# OZ440-SE100-CAR003_Sheet2.net
KiCad netlist of a schematic drawn in Altium Designer
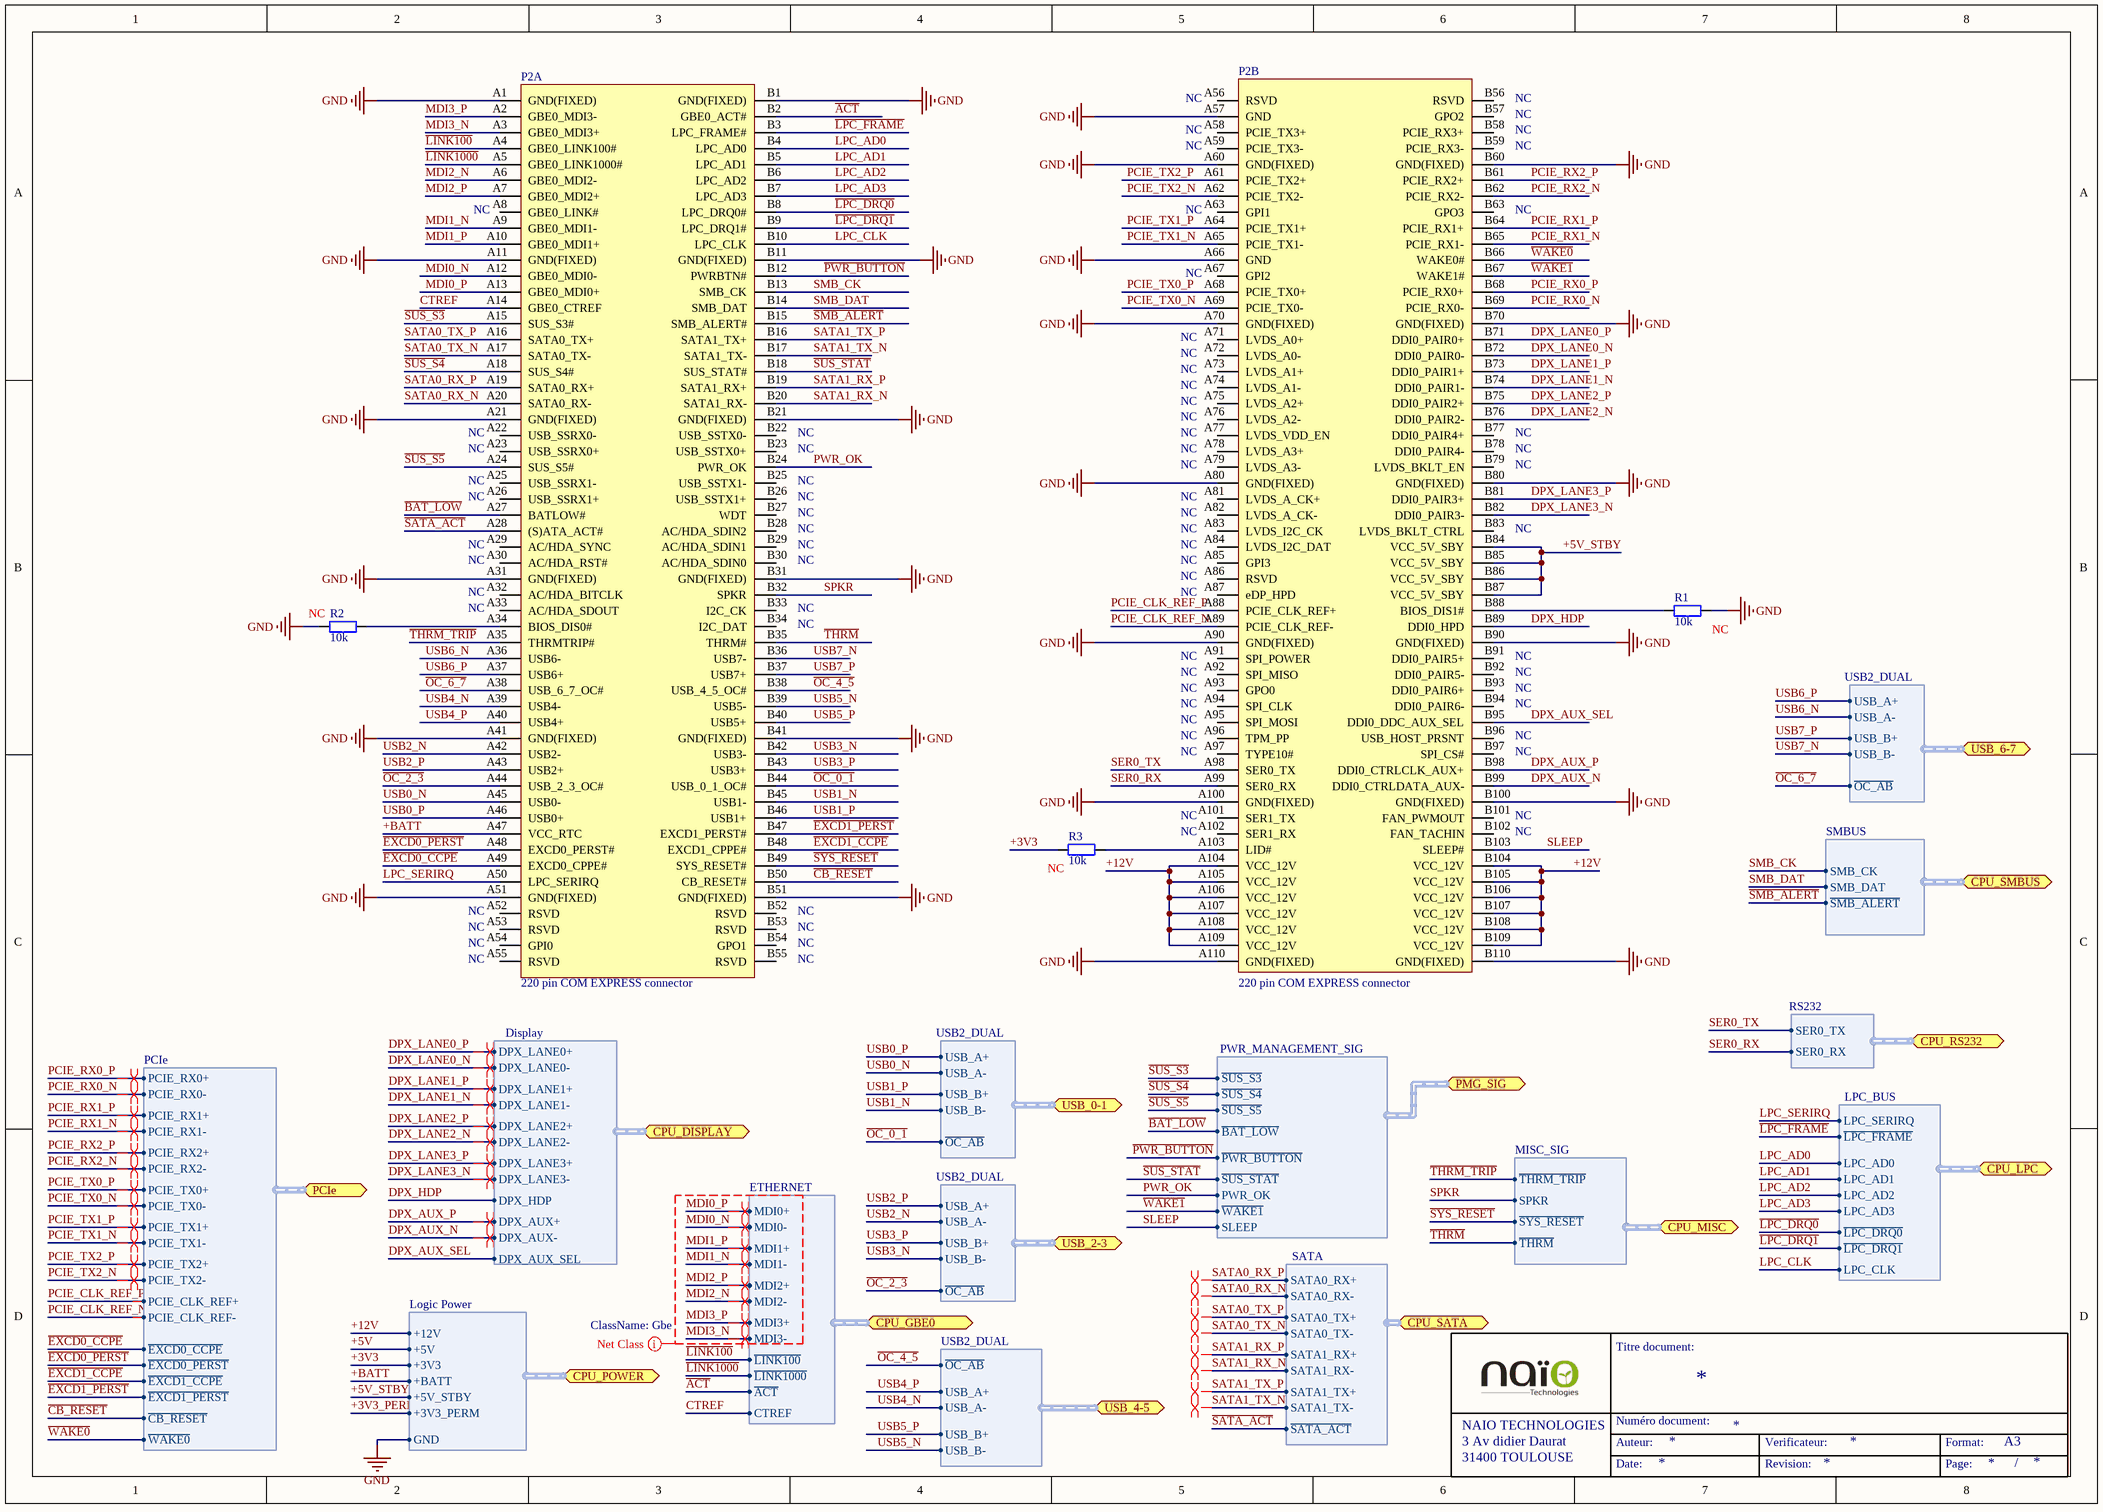
[diagram p0: OZ440-SE100-CAR003_Sheet2.SchDoc]

(export (version "E")
  (design (tool "Eeschema 10.0.6"))
  (components
    (comp (ref "P2")
      (value "CONN-SPE-220P_AMP_3-1827253-6")
      (footprint "CONN-SPE_AMP_3-1827253-6")
      (description "type 10 com express connector")
      (fields
        (field (name "DISPLAYED REFERENCE") "220 pin COM EXPRESS connector")
        (field (name "MANUFACTURER") "TE connectivity")
      )
      (libsource (lib "lib_NAIO") (part "CONN-SPE-220P_AMP_3-1827253-6"))
    )
    (comp (ref "R1")
      (value "RES-SMD")
      (footprint "R0805-STD")
      (description "10k Ohm 0805 SMD resistor")
      (fields
        (field (name "DISPLAYED REFERENCE") "10k")
        (field (name "TOLERANCE") "1 %")
        (field (name "MANUFACTURER") "Vishay")
      )
      (libsource (lib "lib_NAIO") (part "RES-SMD"))
    )
    (comp (ref "R2")
      (value "RES-SMD")
      (footprint "R0805-STD")
      (description "10k Ohm 0805 SMD resistor")
      (fields
        (field (name "DISPLAYED REFERENCE") "10k")
        (field (name "TOLERANCE") "1 %")
        (field (name "MANUFACTURER") "Vishay")
      )
      (libsource (lib "") (part "RES-SMD_1"))
    )
    (comp (ref "R3")
      (value "RES-SMD")
      (footprint "R0805-STD")
      (description "10k Ohm 0805 SMD resistor")
      (fields
        (field (name "DISPLAYED REFERENCE") "10k")
        (field (name "TOLERANCE") "1 %")
        (field (name "MANUFACTURER") "Vishay")
      )
      (libsource (lib "lib_NAIO") (part "RES-SMD"))
    )
  )
  (nets
    (net (code "13") (name "/+3V3") (class "Default")
      (node (ref "R3") (pin "2") (pinfunction "2_2") (pintype "passive"))
    )
    (net (code "16") (name "/+5V_STBY") (class "Default")
      (node (ref "P2") (pin "B84") (pinfunction "VCC_5V_SBY_B84") (pintype "passive"))
      (node (ref "P2") (pin "B85") (pinfunction "VCC_5V_SBY_B85") (pintype "passive"))
      (node (ref "P2") (pin "B86") (pinfunction "VCC_5V_SBY_B86") (pintype "passive"))
      (node (ref "P2") (pin "B87") (pinfunction "VCC_5V_SBY_B87") (pintype "passive"))
    )
    (net (code "17") (name "/+12V") (class "Default")
      (node (ref "P2") (pin "A104") (pinfunction "VCC_12V_A104") (pintype "passive"))
      (node (ref "P2") (pin "A105") (pinfunction "VCC_12V_A105") (pintype "passive"))
      (node (ref "P2") (pin "A106") (pinfunction "VCC_12V_A106") (pintype "passive"))
      (node (ref "P2") (pin "A107") (pinfunction "VCC_12V_A107") (pintype "passive"))
      (node (ref "P2") (pin "A108") (pinfunction "VCC_12V_A108") (pintype "passive"))
      (node (ref "P2") (pin "A109") (pinfunction "VCC_12V_A109") (pintype "passive"))
      (node (ref "P2") (pin "B104") (pinfunction "VCC_12V_B104") (pintype "passive"))
      (node (ref "P2") (pin "B105") (pinfunction "VCC_12V_B105") (pintype "passive"))
      (node (ref "P2") (pin "B106") (pinfunction "VCC_12V_B106") (pintype "passive"))
      (node (ref "P2") (pin "B107") (pinfunction "VCC_12V_B107") (pintype "passive"))
      (node (ref "P2") (pin "B108") (pinfunction "VCC_12V_B108") (pintype "passive"))
      (node (ref "P2") (pin "B109") (pinfunction "VCC_12V_B109") (pintype "passive"))
    )
    (net (code "18") (name "/+BATT") (class "Default")
      (node (ref "P2") (pin "A47") (pinfunction "VCC_RTC_A47") (pintype "passive"))
    )
    (net (code "19") (name "/ACT") (class "Default")
      (node (ref "P2") (pin "B2") (pinfunction "GBE0_ACT#_B2") (pintype "passive"))
    )
    (net (code "20") (name "/BAT_LOW") (class "Default")
      (node (ref "P2") (pin "A27") (pinfunction "BATLOW#_A27") (pintype "passive"))
    )
    (net (code "21") (name "/CB_RESET") (class "Default")
      (node (ref "P2") (pin "B50") (pinfunction "CB_RESET#_B50") (pintype "passive"))
    )
    (net (code "22") (name "/CTREF") (class "Default")
      (node (ref "P2") (pin "A14") (pinfunction "GBE0_CTREF_A14") (pintype "passive"))
    )
    (net (code "23") (name "/DPX_AUX_N") (class "Default")
      (node (ref "P2") (pin "B99") (pinfunction "DDI0_CTRLDATA_AUX-_B99") (pintype "passive"))
    )
    (net (code "24") (name "/DPX_AUX_P") (class "Default")
      (node (ref "P2") (pin "B98") (pinfunction "DDI0_CTRLCLK_AUX+_B98") (pintype "passive"))
    )
    (net (code "25") (name "/DPX_AUX_SEL") (class "Default")
      (node (ref "P2") (pin "B95") (pinfunction "DDI0_DDC_AUX_SEL_B95") (pintype "passive"))
    )
    (net (code "26") (name "/DPX_HDP") (class "Default")
      (node (ref "P2") (pin "B89") (pinfunction "DDI0_HPD_B89") (pintype "passive"))
    )
    (net (code "27") (name "/DPX_LANE0_N") (class "Default")
      (node (ref "P2") (pin "B72") (pinfunction "DDI0_PAIR0-_B72") (pintype "passive"))
    )
    (net (code "28") (name "/DPX_LANE0_P") (class "Default")
      (node (ref "P2") (pin "B71") (pinfunction "DDI0_PAIR0+_B71") (pintype "passive"))
    )
    (net (code "29") (name "/DPX_LANE1_N") (class "Default")
      (node (ref "P2") (pin "B74") (pinfunction "DDI0_PAIR1-_B74") (pintype "passive"))
    )
    (net (code "30") (name "/DPX_LANE1_P") (class "Default")
      (node (ref "P2") (pin "B73") (pinfunction "DDI0_PAIR1+_B73") (pintype "passive"))
    )
    (net (code "31") (name "/DPX_LANE2_N") (class "Default")
      (node (ref "P2") (pin "B76") (pinfunction "DDI0_PAIR2-_B76") (pintype "passive"))
    )
    (net (code "32") (name "/DPX_LANE2_P") (class "Default")
      (node (ref "P2") (pin "B75") (pinfunction "DDI0_PAIR2+_B75") (pintype "passive"))
    )
    (net (code "33") (name "/DPX_LANE3_N") (class "Default")
      (node (ref "P2") (pin "B82") (pinfunction "DDI0_PAIR3-_B82") (pintype "passive"))
    )
    (net (code "34") (name "/DPX_LANE3_P") (class "Default")
      (node (ref "P2") (pin "B81") (pinfunction "DDI0_PAIR3+_B81") (pintype "passive"))
    )
    (net (code "35") (name "/EXCD0_CCPE") (class "Default")
      (node (ref "P2") (pin "A49") (pinfunction "EXCD0_CPPE#_A49") (pintype "passive"))
    )
    (net (code "36") (name "/EXCD0_PERST") (class "Default")
      (node (ref "P2") (pin "A48") (pinfunction "EXCD0_PERST#_A48") (pintype "passive"))
    )
    (net (code "37") (name "/EXCD1_CCPE") (class "Default")
      (node (ref "P2") (pin "B48") (pinfunction "EXCD1_CPPE#_B48") (pintype "passive"))
    )
    (net (code "38") (name "/EXCD1_PERST") (class "Default")
      (node (ref "P2") (pin "B47") (pinfunction "EXCD1_PERST#_B47") (pintype "passive"))
    )
    (net (code "39") (name "/LINK100") (class "Default")
      (node (ref "P2") (pin "A4") (pinfunction "GBE0_LINK100#_A4") (pintype "passive"))
    )
    (net (code "40") (name "/LINK1000") (class "Default")
      (node (ref "P2") (pin "A5") (pinfunction "GBE0_LINK1000#_A5") (pintype "passive"))
    )
    (net (code "41") (name "/LPC_AD0") (class "Default")
      (node (ref "P2") (pin "B4") (pinfunction "LPC_AD0_B4") (pintype "passive"))
    )
    (net (code "42") (name "/LPC_AD1") (class "Default")
      (node (ref "P2") (pin "B5") (pinfunction "LPC_AD1_B5") (pintype "passive"))
    )
    (net (code "43") (name "/LPC_AD2") (class "Default")
      (node (ref "P2") (pin "B6") (pinfunction "LPC_AD2_B6") (pintype "passive"))
    )
    (net (code "44") (name "/LPC_AD3") (class "Default")
      (node (ref "P2") (pin "B7") (pinfunction "LPC_AD3_B7") (pintype "passive"))
    )
    (net (code "45") (name "/LPC_CLK") (class "Default")
      (node (ref "P2") (pin "B10") (pinfunction "LPC_CLK_B10") (pintype "passive"))
    )
    (net (code "46") (name "/LPC_DRQ0") (class "Default")
      (node (ref "P2") (pin "B8") (pinfunction "LPC_DRQ0#_B8") (pintype "passive"))
    )
    (net (code "47") (name "/LPC_DRQ1") (class "Default")
      (node (ref "P2") (pin "B9") (pinfunction "LPC_DRQ1#_B9") (pintype "passive"))
    )
    (net (code "48") (name "/LPC_FRAME") (class "Default")
      (node (ref "P2") (pin "B3") (pinfunction "LPC_FRAME#_B3") (pintype "passive"))
    )
    (net (code "49") (name "/LPC_SERIRQ") (class "Default")
      (node (ref "P2") (pin "A50") (pinfunction "LPC_SERIRQ_A50") (pintype "passive"))
    )
    (net (code "50") (name "/MDI0_N") (class "Default")
      (node (ref "P2") (pin "A12") (pinfunction "GBE0_MDI0-_A12") (pintype "passive"))
    )
    (net (code "51") (name "/MDI0_P") (class "Default")
      (node (ref "P2") (pin "A13") (pinfunction "GBE0_MDI0+_A13") (pintype "passive"))
    )
    (net (code "52") (name "/MDI1_N") (class "Default")
      (node (ref "P2") (pin "A9") (pinfunction "GBE0_MDI1-_A9") (pintype "passive"))
    )
    (net (code "53") (name "/MDI1_P") (class "Default")
      (node (ref "P2") (pin "A10") (pinfunction "GBE0_MDI1+_A10") (pintype "passive"))
    )
    (net (code "54") (name "/MDI2_N") (class "Default")
      (node (ref "P2") (pin "A6") (pinfunction "GBE0_MDI2-_A6") (pintype "passive"))
    )
    (net (code "55") (name "/MDI2_P") (class "Default")
      (node (ref "P2") (pin "A7") (pinfunction "GBE0_MDI2+_A7") (pintype "passive"))
    )
    (net (code "56") (name "/MDI3_N") (class "Default")
      (node (ref "P2") (pin "A3") (pinfunction "GBE0_MDI3+_A3") (pintype "passive"))
    )
    (net (code "57") (name "/MDI3_P") (class "Default")
      (node (ref "P2") (pin "A2") (pinfunction "GBE0_MDI3-_A2") (pintype "passive"))
    )
    (net (code "58") (name "/OC_0_1") (class "Default")
      (node (ref "P2") (pin "B44") (pinfunction "USB_0_1_OC#_B44") (pintype "passive"))
    )
    (net (code "59") (name "/OC_2_3") (class "Default")
      (node (ref "P2") (pin "A44") (pinfunction "USB_2_3_OC#_A44") (pintype "passive"))
    )
    (net (code "60") (name "/OC_4_5") (class "Default")
      (node (ref "P2") (pin "B38") (pinfunction "USB_4_5_OC#_B38") (pintype "passive"))
    )
    (net (code "61") (name "/OC_6_7") (class "Default")
      (node (ref "P2") (pin "A38") (pinfunction "USB_6_7_OC#_A38") (pintype "passive"))
    )
    (net (code "62") (name "/PCIE_CLK_REF_N") (class "Default")
      (node (ref "P2") (pin "A89") (pinfunction "PCIE_CLK_REF-_A89") (pintype "passive"))
    )
    (net (code "63") (name "/PCIE_CLK_REF_P") (class "Default")
      (node (ref "P2") (pin "A88") (pinfunction "PCIE_CLK_REF+_A88") (pintype "passive"))
    )
    (net (code "64") (name "/PCIE_RX0_N") (class "Default")
      (node (ref "P2") (pin "B69") (pinfunction "PCIE_RX0-_B69") (pintype "passive"))
    )
    (net (code "65") (name "/PCIE_RX0_P") (class "Default")
      (node (ref "P2") (pin "B68") (pinfunction "PCIE_RX0+_B68") (pintype "passive"))
    )
    (net (code "66") (name "/PCIE_RX1_N") (class "Default")
      (node (ref "P2") (pin "B65") (pinfunction "PCIE_RX1-_B65") (pintype "passive"))
    )
    (net (code "67") (name "/PCIE_RX1_P") (class "Default")
      (node (ref "P2") (pin "B64") (pinfunction "PCIE_RX1+_B64") (pintype "passive"))
    )
    (net (code "68") (name "/PCIE_RX2_N") (class "Default")
      (node (ref "P2") (pin "B62") (pinfunction "PCIE_RX2-_B62") (pintype "passive"))
    )
    (net (code "69") (name "/PCIE_RX2_P") (class "Default")
      (node (ref "P2") (pin "B61") (pinfunction "PCIE_RX2+_B61") (pintype "passive"))
    )
    (net (code "70") (name "/PCIE_TX0_N") (class "Default")
      (node (ref "P2") (pin "A69") (pinfunction "PCIE_TX0-_A69") (pintype "passive"))
    )
    (net (code "71") (name "/PCIE_TX0_P") (class "Default")
      (node (ref "P2") (pin "A68") (pinfunction "PCIE_TX0+_A68") (pintype "passive"))
    )
    (net (code "72") (name "/PCIE_TX1_N") (class "Default")
      (node (ref "P2") (pin "A65") (pinfunction "PCIE_TX1-_A65") (pintype "passive"))
    )
    (net (code "73") (name "/PCIE_TX1_P") (class "Default")
      (node (ref "P2") (pin "A64") (pinfunction "PCIE_TX1+_A64") (pintype "passive"))
    )
    (net (code "74") (name "/PCIE_TX2_N") (class "Default")
      (node (ref "P2") (pin "A62") (pinfunction "PCIE_TX2-_A62") (pintype "passive"))
    )
    (net (code "75") (name "/PCIE_TX2_P") (class "Default")
      (node (ref "P2") (pin "A61") (pinfunction "PCIE_TX2+_A61") (pintype "passive"))
    )
    (net (code "76") (name "/PWR_BUTTON") (class "Default")
      (node (ref "P2") (pin "B12") (pinfunction "PWRBTN#_B12") (pintype "passive"))
    )
    (net (code "77") (name "/PWR_OK") (class "Default")
      (node (ref "P2") (pin "B24") (pinfunction "PWR_OK_B24") (pintype "passive"))
    )
    (net (code "78") (name "/SATA0_RX_N") (class "Default")
      (node (ref "P2") (pin "A20") (pinfunction "SATA0_RX-_A20") (pintype "passive"))
    )
    (net (code "79") (name "/SATA0_RX_P") (class "Default")
      (node (ref "P2") (pin "A19") (pinfunction "SATA0_RX+_A19") (pintype "passive"))
    )
    (net (code "80") (name "/SATA0_TX_N") (class "Default")
      (node (ref "P2") (pin "A17") (pinfunction "SATA0_TX-_A17") (pintype "passive"))
    )
    (net (code "81") (name "/SATA0_TX_P") (class "Default")
      (node (ref "P2") (pin "A16") (pinfunction "SATA0_TX+_A16") (pintype "passive"))
    )
    (net (code "82") (name "/SATA1_RX_N") (class "Default")
      (node (ref "P2") (pin "B20") (pinfunction "SATA1_RX-_B20") (pintype "passive"))
    )
    (net (code "83") (name "/SATA1_RX_P") (class "Default")
      (node (ref "P2") (pin "B19") (pinfunction "SATA1_RX+_B19") (pintype "passive"))
    )
    (net (code "84") (name "/SATA1_TX_N") (class "Default")
      (node (ref "P2") (pin "B17") (pinfunction "SATA1_TX-_B17") (pintype "passive"))
    )
    (net (code "85") (name "/SATA1_TX_P") (class "Default")
      (node (ref "P2") (pin "B16") (pinfunction "SATA1_TX+_B16") (pintype "passive"))
    )
    (net (code "86") (name "/SATA_ACT") (class "Default")
      (node (ref "P2") (pin "A28") (pinfunction "(S)ATA_ACT#_A28") (pintype "passive"))
    )
    (net (code "87") (name "/SER0_RX") (class "Default")
      (node (ref "P2") (pin "A99") (pinfunction "SER0_RX_A99") (pintype "passive"))
    )
    (net (code "88") (name "/SER0_TX") (class "Default")
      (node (ref "P2") (pin "A98") (pinfunction "SER0_TX_A98") (pintype "passive"))
    )
    (net (code "89") (name "/SLEEP") (class "Default")
      (node (ref "P2") (pin "B103") (pinfunction "SLEEP#_B103") (pintype "passive"))
    )
    (net (code "90") (name "/SMB_ALERT") (class "Default")
      (node (ref "P2") (pin "B15") (pinfunction "SMB_ALERT#_B15") (pintype "passive"))
    )
    (net (code "91") (name "/SMB_CK") (class "Default")
      (node (ref "P2") (pin "B13") (pinfunction "SMB_CK_B13") (pintype "passive"))
    )
    (net (code "92") (name "/SMB_DAT") (class "Default")
      (node (ref "P2") (pin "B14") (pinfunction "SMB_DAT_B14") (pintype "passive"))
    )
    (net (code "93") (name "/SPKR") (class "Default")
      (node (ref "P2") (pin "B32") (pinfunction "SPKR_B32") (pintype "passive"))
    )
    (net (code "94") (name "/SUS_S3") (class "Default")
      (node (ref "P2") (pin "A15") (pinfunction "SUS_S3#_A15") (pintype "passive"))
    )
    (net (code "95") (name "/SUS_S4") (class "Default")
      (node (ref "P2") (pin "A18") (pinfunction "SUS_S4#_A18") (pintype "passive"))
    )
    (net (code "96") (name "/SUS_S5") (class "Default")
      (node (ref "P2") (pin "A24") (pinfunction "SUS_S5#_A24") (pintype "passive"))
    )
    (net (code "97") (name "/SUS_STAT") (class "Default")
      (node (ref "P2") (pin "B18") (pinfunction "SUS_STAT#_B18") (pintype "passive"))
    )
    (net (code "98") (name "/SYS_RESET") (class "Default")
      (node (ref "P2") (pin "B49") (pinfunction "SYS_RESET#_B49") (pintype "passive"))
    )
    (net (code "99") (name "/THRM") (class "Default")
      (node (ref "P2") (pin "B35") (pinfunction "THRM#_B35") (pintype "passive"))
    )
    (net (code "100") (name "/THRM_TRIP") (class "Default")
      (node (ref "P2") (pin "A35") (pinfunction "THRMTRIP#_A35") (pintype "passive"))
    )
    (net (code "101") (name "/USB0_N") (class "Default")
      (node (ref "P2") (pin "A45") (pinfunction "USB0-_A45") (pintype "passive"))
    )
    (net (code "102") (name "/USB0_P") (class "Default")
      (node (ref "P2") (pin "A46") (pinfunction "USB0+_A46") (pintype "passive"))
    )
    (net (code "103") (name "/USB1_N") (class "Default")
      (node (ref "P2") (pin "B45") (pinfunction "USB1-_B45") (pintype "passive"))
    )
    (net (code "104") (name "/USB1_P") (class "Default")
      (node (ref "P2") (pin "B46") (pinfunction "USB1+_B46") (pintype "passive"))
    )
    (net (code "105") (name "/USB2_N") (class "Default")
      (node (ref "P2") (pin "A42") (pinfunction "USB2-_A42") (pintype "passive"))
    )
    (net (code "106") (name "/USB2_P") (class "Default")
      (node (ref "P2") (pin "A43") (pinfunction "USB2+_A43") (pintype "passive"))
    )
    (net (code "107") (name "/USB3_N") (class "Default")
      (node (ref "P2") (pin "B42") (pinfunction "USB3-_B42") (pintype "passive"))
    )
    (net (code "108") (name "/USB3_P") (class "Default")
      (node (ref "P2") (pin "B43") (pinfunction "USB3+_B43") (pintype "passive"))
    )
    (net (code "109") (name "/USB4_N") (class "Default")
      (node (ref "P2") (pin "A39") (pinfunction "USB4-_A39") (pintype "passive"))
    )
    (net (code "110") (name "/USB4_P") (class "Default")
      (node (ref "P2") (pin "A40") (pinfunction "USB4+_A40") (pintype "passive"))
    )
    (net (code "111") (name "/USB5_N") (class "Default")
      (node (ref "P2") (pin "B39") (pinfunction "USB5-_B39") (pintype "passive"))
    )
    (net (code "112") (name "/USB5_P") (class "Default")
      (node (ref "P2") (pin "B40") (pinfunction "USB5+_B40") (pintype "passive"))
    )
    (net (code "113") (name "/USB6_N") (class "Default")
      (node (ref "P2") (pin "A36") (pinfunction "USB6-_A36") (pintype "passive"))
    )
    (net (code "114") (name "/USB6_P") (class "Default")
      (node (ref "P2") (pin "A37") (pinfunction "USB6+_A37") (pintype "passive"))
    )
    (net (code "115") (name "/USB7_N") (class "Default")
      (node (ref "P2") (pin "B36") (pinfunction "USB7-_B36") (pintype "passive"))
    )
    (net (code "116") (name "/USB7_P") (class "Default")
      (node (ref "P2") (pin "B37") (pinfunction "USB7+_B37") (pintype "passive"))
    )
    (net (code "117") (name "/WAKE0") (class "Default")
      (node (ref "P2") (pin "B66") (pinfunction "WAKE0#_B66") (pintype "passive"))
    )
    (net (code "118") (name "/WAKE1") (class "Default")
      (node (ref "P2") (pin "B67") (pinfunction "WAKE1#_B67") (pintype "passive"))
    )
    (net (code "130") (name "GND") (class "Default")
      (node (ref "P2") (pin "A1") (pinfunction "GND(FIXED)_A1") (pintype "passive"))
      (node (ref "P2") (pin "A100") (pinfunction "GND(FIXED)_A100") (pintype "passive"))
      (node (ref "P2") (pin "A11") (pinfunction "GND(FIXED)_A11") (pintype "passive"))
      (node (ref "P2") (pin "A110") (pinfunction "GND(FIXED)_A110") (pintype "passive"))
      (node (ref "P2") (pin "A21") (pinfunction "GND(FIXED)_A21") (pintype "passive"))
      (node (ref "P2") (pin "A31") (pinfunction "GND(FIXED)_A31") (pintype "passive"))
      (node (ref "P2") (pin "A41") (pinfunction "GND(FIXED)_A41") (pintype "passive"))
      (node (ref "P2") (pin "A51") (pinfunction "GND(FIXED)_A51") (pintype "passive"))
      (node (ref "P2") (pin "A57") (pinfunction "GND_A57") (pintype "passive"))
      (node (ref "P2") (pin "A60") (pinfunction "GND(FIXED)_A60") (pintype "passive"))
      (node (ref "P2") (pin "A66") (pinfunction "GND_A66") (pintype "passive"))
      (node (ref "P2") (pin "A70") (pinfunction "GND(FIXED)_A70") (pintype "passive"))
      (node (ref "P2") (pin "A80") (pinfunction "GND(FIXED)_A80") (pintype "passive"))
      (node (ref "P2") (pin "A90") (pinfunction "GND(FIXED)_A90") (pintype "passive"))
      (node (ref "P2") (pin "B1") (pinfunction "GND(FIXED)_B1") (pintype "passive"))
      (node (ref "P2") (pin "B100") (pinfunction "GND(FIXED)_B100") (pintype "passive"))
      (node (ref "P2") (pin "B11") (pinfunction "GND(FIXED)_B11") (pintype "passive"))
      (node (ref "P2") (pin "B110") (pinfunction "GND(FIXED)_B110") (pintype "passive"))
      (node (ref "P2") (pin "B21") (pinfunction "GND(FIXED)_B21") (pintype "passive"))
      (node (ref "P2") (pin "B31") (pinfunction "GND(FIXED)_B31") (pintype "passive"))
      (node (ref "P2") (pin "B41") (pinfunction "GND(FIXED)_B41") (pintype "passive"))
      (node (ref "P2") (pin "B51") (pinfunction "GND(FIXED)_B51") (pintype "passive"))
      (node (ref "P2") (pin "B60") (pinfunction "GND(FIXED)_B60") (pintype "passive"))
      (node (ref "P2") (pin "B70") (pinfunction "GND(FIXED)_B70") (pintype "passive"))
      (node (ref "P2") (pin "B80") (pinfunction "GND(FIXED)_B80") (pintype "passive"))
      (node (ref "P2") (pin "B90") (pinfunction "GND(FIXED)_B90") (pintype "passive"))
      (node (ref "R1") (pin "1") (pinfunction "1_1") (pintype "passive"))
      (node (ref "R2") (pin "1") (pinfunction "1_1") (pintype "passive"))
    )
    (net (code "131") (name "Net-(P2A-BIOS_DIS0#)") (class "Default")
      (node (ref "P2") (pin "A34") (pinfunction "BIOS_DIS0#_A34") (pintype "passive"))
      (node (ref "R2") (pin "2") (pinfunction "2_2") (pintype "passive"))
    )
    (net (code "132") (name "Net-(P2B-BIOS_DIS1#)") (class "Default")
      (node (ref "P2") (pin "B88") (pinfunction "BIOS_DIS1#_B88") (pintype "passive"))
      (node (ref "R1") (pin "2") (pinfunction "2_2") (pintype "passive"))
    )
    (net (code "133") (name "Net-(P2B-LID#)") (class "Default")
      (node (ref "P2") (pin "A103") (pinfunction "LID#_A103") (pintype "passive"))
      (node (ref "R3") (pin "1") (pinfunction "1_1") (pintype "passive"))
    )
    (net (code "134") (name "unconnected-(P2A-AC{slash}HDA_BITCLK-PadA32)") (class "Default")
      (node (ref "P2") (pin "A32") (pinfunction "AC/HDA_BITCLK_A32") (pintype "passive"))
    )
    (net (code "135") (name "unconnected-(P2A-AC{slash}HDA_RST#-PadA30)") (class "Default")
      (node (ref "P2") (pin "A30") (pinfunction "AC/HDA_RST#_A30") (pintype "passive"))
    )
    (net (code "136") (name "unconnected-(P2A-AC{slash}HDA_SDIN0-PadB30)") (class "Default")
      (node (ref "P2") (pin "B30") (pinfunction "AC/HDA_SDIN0_B30") (pintype "passive"))
    )
    (net (code "137") (name "unconnected-(P2A-AC{slash}HDA_SDIN1-PadB29)") (class "Default")
      (node (ref "P2") (pin "B29") (pinfunction "AC/HDA_SDIN1_B29") (pintype "passive"))
    )
    (net (code "138") (name "unconnected-(P2A-AC{slash}HDA_SDIN2-PadB28)") (class "Default")
      (node (ref "P2") (pin "B28") (pinfunction "AC/HDA_SDIN2_B28") (pintype "passive"))
    )
    (net (code "139") (name "unconnected-(P2A-AC{slash}HDA_SDOUT-PadA33)") (class "Default")
      (node (ref "P2") (pin "A33") (pinfunction "AC/HDA_SDOUT_A33") (pintype "passive"))
    )
    (net (code "140") (name "unconnected-(P2A-AC{slash}HDA_SYNC-PadA29)") (class "Default")
      (node (ref "P2") (pin "A29") (pinfunction "AC/HDA_SYNC_A29") (pintype "passive"))
    )
    (net (code "141") (name "unconnected-(P2A-GBE0_LINK#-PadA8)") (class "Default")
      (node (ref "P2") (pin "A8") (pinfunction "GBE0_LINK#_A8") (pintype "passive"))
    )
    (net (code "142") (name "unconnected-(P2A-GPI0-PadA54)") (class "Default")
      (node (ref "P2") (pin "A54") (pinfunction "GPI0_A54") (pintype "passive"))
    )
    (net (code "143") (name "unconnected-(P2A-GPO1-PadB54)") (class "Default")
      (node (ref "P2") (pin "B54") (pinfunction "GPO1_B54") (pintype "passive"))
    )
    (net (code "144") (name "unconnected-(P2A-I2C_CK-PadB33)") (class "Default")
      (node (ref "P2") (pin "B33") (pinfunction "I2C_CK_B33") (pintype "passive"))
    )
    (net (code "145") (name "unconnected-(P2A-I2C_DAT-PadB34)") (class "Default")
      (node (ref "P2") (pin "B34") (pinfunction "I2C_DAT_B34") (pintype "passive"))
    )
    (net (code "146") (name "unconnected-(P2A-RSVD-PadA52)") (class "Default")
      (node (ref "P2") (pin "A52") (pinfunction "RSVD_A52") (pintype "passive"))
    )
    (net (code "147") (name "unconnected-(P2A-RSVD-PadA53)") (class "Default")
      (node (ref "P2") (pin "A53") (pinfunction "RSVD_A53") (pintype "passive"))
    )
    (net (code "148") (name "unconnected-(P2A-RSVD-PadA55)") (class "Default")
      (node (ref "P2") (pin "A55") (pinfunction "RSVD_A55") (pintype "passive"))
    )
    (net (code "149") (name "unconnected-(P2A-RSVD-PadB52)") (class "Default")
      (node (ref "P2") (pin "B52") (pinfunction "RSVD_B52") (pintype "passive"))
    )
    (net (code "150") (name "unconnected-(P2A-RSVD-PadB53)") (class "Default")
      (node (ref "P2") (pin "B53") (pinfunction "RSVD_B53") (pintype "passive"))
    )
    (net (code "151") (name "unconnected-(P2A-RSVD-PadB55)") (class "Default")
      (node (ref "P2") (pin "B55") (pinfunction "RSVD_B55") (pintype "passive"))
    )
    (net (code "152") (name "unconnected-(P2A-USB_SSRX0+-PadA23)") (class "Default")
      (node (ref "P2") (pin "A23") (pinfunction "USB_SSRX0+_A23") (pintype "passive"))
    )
    (net (code "153") (name "unconnected-(P2A-USB_SSRX0--PadA22)") (class "Default")
      (node (ref "P2") (pin "A22") (pinfunction "USB_SSRX0-_A22") (pintype "passive"))
    )
    (net (code "154") (name "unconnected-(P2A-USB_SSRX1+-PadA26)") (class "Default")
      (node (ref "P2") (pin "A26") (pinfunction "USB_SSRX1+_A26") (pintype "passive"))
    )
    (net (code "155") (name "unconnected-(P2A-USB_SSRX1--PadA25)") (class "Default")
      (node (ref "P2") (pin "A25") (pinfunction "USB_SSRX1-_A25") (pintype "passive"))
    )
    (net (code "156") (name "unconnected-(P2A-USB_SSTX0+-PadB23)") (class "Default")
      (node (ref "P2") (pin "B23") (pinfunction "USB_SSTX0+_B23") (pintype "passive"))
    )
    (net (code "157") (name "unconnected-(P2A-USB_SSTX0--PadB22)") (class "Default")
      (node (ref "P2") (pin "B22") (pinfunction "USB_SSTX0-_B22") (pintype "passive"))
    )
    (net (code "158") (name "unconnected-(P2A-USB_SSTX1+-PadB26)") (class "Default")
      (node (ref "P2") (pin "B26") (pinfunction "USB_SSTX1+_B26") (pintype "passive"))
    )
    (net (code "159") (name "unconnected-(P2A-USB_SSTX1--PadB25)") (class "Default")
      (node (ref "P2") (pin "B25") (pinfunction "USB_SSTX1-_B25") (pintype "passive"))
    )
    (net (code "160") (name "unconnected-(P2A-WDT-PadB27)") (class "Default")
      (node (ref "P2") (pin "B27") (pinfunction "WDT_B27") (pintype "passive"))
    )
    (net (code "161") (name "unconnected-(P2B-DDI0_PAIR4+-PadB77)") (class "Default")
      (node (ref "P2") (pin "B77") (pinfunction "DDI0_PAIR4+_B77") (pintype "passive"))
    )
    (net (code "162") (name "unconnected-(P2B-DDI0_PAIR4--PadB78)") (class "Default")
      (node (ref "P2") (pin "B78") (pinfunction "DDI0_PAIR4-_B78") (pintype "passive"))
    )
    (net (code "163") (name "unconnected-(P2B-DDI0_PAIR5+-PadB91)") (class "Default")
      (node (ref "P2") (pin "B91") (pinfunction "DDI0_PAIR5+_B91") (pintype "passive"))
    )
    (net (code "164") (name "unconnected-(P2B-DDI0_PAIR5--PadB92)") (class "Default")
      (node (ref "P2") (pin "B92") (pinfunction "DDI0_PAIR5-_B92") (pintype "passive"))
    )
    (net (code "165") (name "unconnected-(P2B-DDI0_PAIR6+-PadB93)") (class "Default")
      (node (ref "P2") (pin "B93") (pinfunction "DDI0_PAIR6+_B93") (pintype "passive"))
    )
    (net (code "166") (name "unconnected-(P2B-DDI0_PAIR6--PadB94)") (class "Default")
      (node (ref "P2") (pin "B94") (pinfunction "DDI0_PAIR6-_B94") (pintype "passive"))
    )
    (net (code "167") (name "unconnected-(P2B-FAN_PWMOUT-PadB101)") (class "Default")
      (node (ref "P2") (pin "B101") (pinfunction "FAN_PWMOUT_B101") (pintype "passive"))
    )
    (net (code "168") (name "unconnected-(P2B-FAN_TACHIN-PadB102)") (class "Default")
      (node (ref "P2") (pin "B102") (pinfunction "FAN_TACHIN_B102") (pintype "passive"))
    )
    (net (code "169") (name "unconnected-(P2B-GPI1-PadA63)") (class "Default")
      (node (ref "P2") (pin "A63") (pinfunction "GPI1_A63") (pintype "passive"))
    )
    (net (code "170") (name "unconnected-(P2B-GPI2-PadA67)") (class "Default")
      (node (ref "P2") (pin "A67") (pinfunction "GPI2_A67") (pintype "passive"))
    )
    (net (code "171") (name "unconnected-(P2B-GPI3-PadA85)") (class "Default")
      (node (ref "P2") (pin "A85") (pinfunction "GPI3_A85") (pintype "passive"))
    )
    (net (code "172") (name "unconnected-(P2B-GPO0-PadA93)") (class "Default")
      (node (ref "P2") (pin "A93") (pinfunction "GPO0_A93") (pintype "passive"))
    )
    (net (code "173") (name "unconnected-(P2B-GPO2-PadB57)") (class "Default")
      (node (ref "P2") (pin "B57") (pinfunction "GPO2_B57") (pintype "passive"))
    )
    (net (code "174") (name "unconnected-(P2B-GPO3-PadB63)") (class "Default")
      (node (ref "P2") (pin "B63") (pinfunction "GPO3_B63") (pintype "passive"))
    )
    (net (code "175") (name "unconnected-(P2B-LVDS_A0+-PadA71)") (class "Default")
      (node (ref "P2") (pin "A71") (pinfunction "LVDS_A0+_A71") (pintype "passive"))
    )
    (net (code "176") (name "unconnected-(P2B-LVDS_A0--PadA72)") (class "Default")
      (node (ref "P2") (pin "A72") (pinfunction "LVDS_A0-_A72") (pintype "passive"))
    )
    (net (code "177") (name "unconnected-(P2B-LVDS_A1+-PadA73)") (class "Default")
      (node (ref "P2") (pin "A73") (pinfunction "LVDS_A1+_A73") (pintype "passive"))
    )
    (net (code "178") (name "unconnected-(P2B-LVDS_A1--PadA74)") (class "Default")
      (node (ref "P2") (pin "A74") (pinfunction "LVDS_A1-_A74") (pintype "passive"))
    )
    (net (code "179") (name "unconnected-(P2B-LVDS_A2+-PadA75)") (class "Default")
      (node (ref "P2") (pin "A75") (pinfunction "LVDS_A2+_A75") (pintype "passive"))
    )
    (net (code "180") (name "unconnected-(P2B-LVDS_A2--PadA76)") (class "Default")
      (node (ref "P2") (pin "A76") (pinfunction "LVDS_A2-_A76") (pintype "passive"))
    )
    (net (code "181") (name "unconnected-(P2B-LVDS_A3+-PadA78)") (class "Default")
      (node (ref "P2") (pin "A78") (pinfunction "LVDS_A3+_A78") (pintype "passive"))
    )
    (net (code "182") (name "unconnected-(P2B-LVDS_A3--PadA79)") (class "Default")
      (node (ref "P2") (pin "A79") (pinfunction "LVDS_A3-_A79") (pintype "passive"))
    )
    (net (code "183") (name "unconnected-(P2B-LVDS_A_CK+-PadA81)") (class "Default")
      (node (ref "P2") (pin "A81") (pinfunction "LVDS_A_CK+_A81") (pintype "passive"))
    )
    (net (code "184") (name "unconnected-(P2B-LVDS_A_CK--PadA82)") (class "Default")
      (node (ref "P2") (pin "A82") (pinfunction "LVDS_A_CK-_A82") (pintype "passive"))
    )
    (net (code "185") (name "unconnected-(P2B-LVDS_BKLT_CTRL-PadB83)") (class "Default")
      (node (ref "P2") (pin "B83") (pinfunction "LVDS_BKLT_CTRL_B83") (pintype "passive"))
    )
    (net (code "186") (name "unconnected-(P2B-LVDS_BKLT_EN-PadB79)") (class "Default")
      (node (ref "P2") (pin "B79") (pinfunction "LVDS_BKLT_EN_B79") (pintype "passive"))
    )
    (net (code "187") (name "unconnected-(P2B-LVDS_I2C_CK-PadA83)") (class "Default")
      (node (ref "P2") (pin "A83") (pinfunction "LVDS_I2C_CK_A83") (pintype "passive"))
    )
    (net (code "188") (name "unconnected-(P2B-LVDS_I2C_DAT-PadA84)") (class "Default")
      (node (ref "P2") (pin "A84") (pinfunction "LVDS_I2C_DAT_A84") (pintype "passive"))
    )
    (net (code "189") (name "unconnected-(P2B-LVDS_VDD_EN-PadA77)") (class "Default")
      (node (ref "P2") (pin "A77") (pinfunction "LVDS_VDD_EN_A77") (pintype "passive"))
    )
    (net (code "190") (name "unconnected-(P2B-PCIE_RX3+-PadB58)") (class "Default")
      (node (ref "P2") (pin "B58") (pinfunction "PCIE_RX3+_B58") (pintype "passive"))
    )
    (net (code "191") (name "unconnected-(P2B-PCIE_RX3--PadB59)") (class "Default")
      (node (ref "P2") (pin "B59") (pinfunction "PCIE_RX3-_B59") (pintype "passive"))
    )
    (net (code "192") (name "unconnected-(P2B-PCIE_TX3+-PadA58)") (class "Default")
      (node (ref "P2") (pin "A58") (pinfunction "PCIE_TX3+_A58") (pintype "passive"))
    )
    (net (code "193") (name "unconnected-(P2B-PCIE_TX3--PadA59)") (class "Default")
      (node (ref "P2") (pin "A59") (pinfunction "PCIE_TX3-_A59") (pintype "passive"))
    )
    (net (code "194") (name "unconnected-(P2B-RSVD-PadA56)") (class "Default")
      (node (ref "P2") (pin "A56") (pinfunction "RSVD_A56") (pintype "passive"))
    )
    (net (code "195") (name "unconnected-(P2B-RSVD-PadA86)") (class "Default")
      (node (ref "P2") (pin "A86") (pinfunction "RSVD_A86") (pintype "passive"))
    )
    (net (code "196") (name "unconnected-(P2B-RSVD-PadB56)") (class "Default")
      (node (ref "P2") (pin "B56") (pinfunction "RSVD_B56") (pintype "passive"))
    )
    (net (code "197") (name "unconnected-(P2B-SER1_RX-PadA102)") (class "Default")
      (node (ref "P2") (pin "A102") (pinfunction "SER1_RX_A102") (pintype "passive"))
    )
    (net (code "198") (name "unconnected-(P2B-SER1_TX-PadA101)") (class "Default")
      (node (ref "P2") (pin "A101") (pinfunction "SER1_TX_A101") (pintype "passive"))
    )
    (net (code "199") (name "unconnected-(P2B-SPI_CLK-PadA94)") (class "Default")
      (node (ref "P2") (pin "A94") (pinfunction "SPI_CLK_A94") (pintype "passive"))
    )
    (net (code "200") (name "unconnected-(P2B-SPI_CS#-PadB97)") (class "Default")
      (node (ref "P2") (pin "B97") (pinfunction "SPI_CS#_B97") (pintype "passive"))
    )
    (net (code "201") (name "unconnected-(P2B-SPI_MISO-PadA92)") (class "Default")
      (node (ref "P2") (pin "A92") (pinfunction "SPI_MISO_A92") (pintype "passive"))
    )
    (net (code "202") (name "unconnected-(P2B-SPI_MOSI-PadA95)") (class "Default")
      (node (ref "P2") (pin "A95") (pinfunction "SPI_MOSI_A95") (pintype "passive"))
    )
    (net (code "203") (name "unconnected-(P2B-SPI_POWER-PadA91)") (class "Default")
      (node (ref "P2") (pin "A91") (pinfunction "SPI_POWER_A91") (pintype "passive"))
    )
    (net (code "204") (name "unconnected-(P2B-TPM_PP-PadA96)") (class "Default")
      (node (ref "P2") (pin "A96") (pinfunction "TPM_PP_A96") (pintype "passive"))
    )
    (net (code "205") (name "unconnected-(P2B-TYPE10#-PadA97)") (class "Default")
      (node (ref "P2") (pin "A97") (pinfunction "TYPE10#_A97") (pintype "passive"))
    )
    (net (code "206") (name "unconnected-(P2B-USB_HOST_PRSNT-PadB96)") (class "Default")
      (node (ref "P2") (pin "B96") (pinfunction "USB_HOST_PRSNT_B96") (pintype "passive"))
    )
    (net (code "207") (name "unconnected-(P2B-eDP_HPD-PadA87)") (class "Default")
      (node (ref "P2") (pin "A87") (pinfunction "eDP_HPD_A87") (pintype "passive"))
    )
  )
)
